# carberry.net
KiCad netlist of a schematic drawn in EAGLE
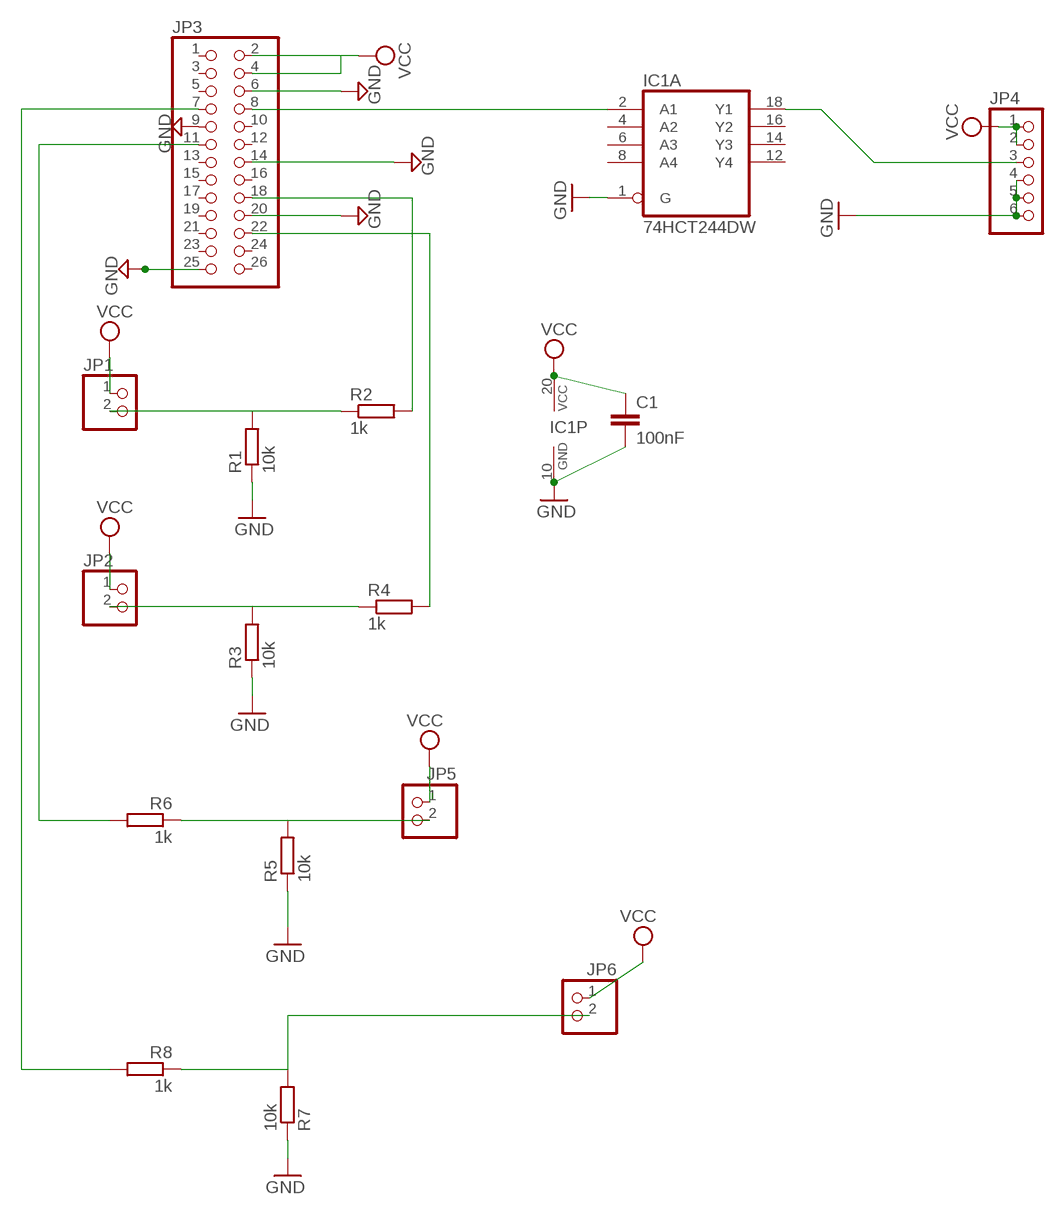
[diagram p0: schematic, sheet 1]

(export (version "E")
  (design (tool "Eeschema 10.0.6"))
  (components
    (comp (ref "C1")
      (value "100nF")
      (footprint "eagle-import:C0603K")
      (libsource (lib "eagle-import") (part "C-EUC0603K"))
    )
    (comp (ref "IC1")
      (value "74HCT244DW")
      (footprint "eagle-import:SO20W")
      (libsource (lib "eagle-import") (part "74244DWHCT"))
    )
    (comp (ref "JP1")
      (value "PINHD-1X2")
      (footprint "eagle-import:1X02")
      (libsource (lib "eagle-import") (part "PINHD-1X2"))
    )
    (comp (ref "JP2")
      (value "PINHD-1X2")
      (footprint "eagle-import:1X02")
      (libsource (lib "eagle-import") (part "PINHD-1X2"))
    )
    (comp (ref "JP3")
      (value "PINHD-2X13")
      (footprint "eagle-import:2X13")
      (libsource (lib "eagle-import") (part "PINHD-2X13"))
    )
    (comp (ref "JP4")
      (value "PINHD-1X6")
      (footprint "eagle-import:1X06")
      (libsource (lib "eagle-import") (part "PINHD-1X6"))
    )
    (comp (ref "JP5")
      (value "PINHD-1X2")
      (footprint "eagle-import:1X02")
      (libsource (lib "eagle-import") (part "PINHD-1X2"))
    )
    (comp (ref "JP6")
      (value "PINHD-1X2")
      (footprint "eagle-import:1X02")
      (libsource (lib "eagle-import") (part "PINHD-1X2"))
    )
    (comp (ref "R1")
      (value "10k")
      (footprint "eagle-import:R0603")
      (libsource (lib "eagle-import") (part "RR0603"))
    )
    (comp (ref "R2")
      (value "1k")
      (footprint "eagle-import:R0603")
      (libsource (lib "eagle-import") (part "RR0603"))
    )
    (comp (ref "R3")
      (value "10k")
      (footprint "eagle-import:R0603")
      (libsource (lib "eagle-import") (part "RR0603"))
    )
    (comp (ref "R4")
      (value "1k")
      (footprint "eagle-import:R0603")
      (libsource (lib "eagle-import") (part "RR0603"))
    )
    (comp (ref "R5")
      (value "10k")
      (footprint "eagle-import:R0603")
      (libsource (lib "eagle-import") (part "RR0603"))
    )
    (comp (ref "R6")
      (value "1k")
      (footprint "eagle-import:R0603")
      (libsource (lib "eagle-import") (part "RR0603"))
    )
    (comp (ref "R7")
      (value "10k")
      (footprint "eagle-import:R0603")
      (libsource (lib "eagle-import") (part "RR0603"))
    )
    (comp (ref "R8")
      (value "1k")
      (footprint "eagle-import:R0603")
      (libsource (lib "eagle-import") (part "RR0603"))
    )
  )
  (nets
    (net (code "1") (name "GND") (class "Default")
      (node (ref "C1") (pin "2") (pinfunction "2_2") (pintype "passive"))
      (node (ref "IC1") (pin "1") (pinfunction "G_1") (pintype "input"))
      (node (ref "IC1") (pin "10") (pinfunction "GND_10") (pintype "power_in"))
      (node (ref "JP3") (pin "14") (pinfunction "14_14") (pintype "passive"))
      (node (ref "JP3") (pin "20") (pinfunction "20_20") (pintype "passive"))
      (node (ref "JP3") (pin "25") (pinfunction "25_25") (pintype "passive"))
      (node (ref "JP3") (pin "6") (pinfunction "6_6") (pintype "passive"))
      (node (ref "JP3") (pin "9") (pinfunction "9_9") (pintype "passive"))
      (node (ref "JP4") (pin "4") (pinfunction "4_4") (pintype "passive"))
      (node (ref "JP4") (pin "5") (pinfunction "5_5") (pintype "passive"))
      (node (ref "JP4") (pin "6") (pinfunction "6_6") (pintype "passive"))
      (node (ref "R1") (pin "1") (pinfunction "1_1") (pintype "passive"))
      (node (ref "R3") (pin "1") (pinfunction "1_1") (pintype "passive"))
      (node (ref "R5") (pin "1") (pinfunction "1_1") (pintype "passive"))
      (node (ref "R7") (pin "1") (pinfunction "1_1") (pintype "passive"))
    )
    (net (code "2") (name "Net-(IC1A-A1)") (class "Default")
      (node (ref "IC1") (pin "2") (pinfunction "A1_2") (pintype "input"))
      (node (ref "JP3") (pin "8") (pinfunction "8_8") (pintype "passive"))
    )
    (net (code "3") (name "Net-(IC1A-Y1)") (class "Default")
      (node (ref "IC1") (pin "18") (pinfunction "Y1_18") (pintype "tri_state"))
      (node (ref "JP4") (pin "3") (pinfunction "3_3") (pintype "passive"))
    )
    (net (code "4") (name "Net-(JP1-Pad2)") (class "Default")
      (node (ref "JP1") (pin "2") (pinfunction "2_2") (pintype "passive"))
      (node (ref "R1") (pin "2") (pinfunction "2_2") (pintype "passive"))
      (node (ref "R2") (pin "1") (pinfunction "1_1") (pintype "passive"))
    )
    (net (code "5") (name "Net-(JP2-Pad2)") (class "Default")
      (node (ref "JP2") (pin "2") (pinfunction "2_2") (pintype "passive"))
      (node (ref "R3") (pin "2") (pinfunction "2_2") (pintype "passive"))
      (node (ref "R4") (pin "1") (pinfunction "1_1") (pintype "passive"))
    )
    (net (code "6") (name "Net-(JP3-Pad7)") (class "Default")
      (node (ref "JP3") (pin "7") (pinfunction "7_7") (pintype "passive"))
      (node (ref "R8") (pin "2") (pinfunction "2_2") (pintype "passive"))
    )
    (net (code "7") (name "Net-(JP3-Pad11)") (class "Default")
      (node (ref "JP3") (pin "11") (pinfunction "11_11") (pintype "passive"))
      (node (ref "R6") (pin "2") (pinfunction "2_2") (pintype "passive"))
    )
    (net (code "8") (name "Net-(JP3-Pad18)") (class "Default")
      (node (ref "JP3") (pin "18") (pinfunction "18_18") (pintype "passive"))
      (node (ref "R2") (pin "2") (pinfunction "2_2") (pintype "passive"))
    )
    (net (code "9") (name "Net-(JP3-Pad22)") (class "Default")
      (node (ref "JP3") (pin "22") (pinfunction "22_22") (pintype "passive"))
      (node (ref "R4") (pin "2") (pinfunction "2_2") (pintype "passive"))
    )
    (net (code "10") (name "Net-(JP5-Pad2)") (class "Default")
      (node (ref "JP5") (pin "2") (pinfunction "2_2") (pintype "passive"))
      (node (ref "R5") (pin "2") (pinfunction "2_2") (pintype "passive"))
      (node (ref "R6") (pin "1") (pinfunction "1_1") (pintype "passive"))
    )
    (net (code "11") (name "Net-(JP6-Pad2)") (class "Default")
      (node (ref "JP6") (pin "2") (pinfunction "2_2") (pintype "passive"))
      (node (ref "R7") (pin "2") (pinfunction "2_2") (pintype "passive"))
      (node (ref "R8") (pin "1") (pinfunction "1_1") (pintype "passive"))
    )
    (net (code "12") (name "VCC") (class "Default")
      (node (ref "C1") (pin "1") (pinfunction "1_1") (pintype "passive"))
      (node (ref "IC1") (pin "20") (pinfunction "VCC_20") (pintype "power_in"))
      (node (ref "JP1") (pin "1") (pinfunction "1_1") (pintype "passive"))
      (node (ref "JP2") (pin "1") (pinfunction "1_1") (pintype "passive"))
      (node (ref "JP3") (pin "2") (pinfunction "2_2") (pintype "passive"))
      (node (ref "JP3") (pin "4") (pinfunction "4_4") (pintype "passive"))
      (node (ref "JP4") (pin "1") (pinfunction "1_1") (pintype "passive"))
      (node (ref "JP4") (pin "2") (pinfunction "2_2") (pintype "passive"))
      (node (ref "JP5") (pin "1") (pinfunction "1_1") (pintype "passive"))
      (node (ref "JP6") (pin "1") (pinfunction "1_1") (pintype "passive"))
    )
    (net (code "13") (name "unconnected-(IC1A-A2-Pad4)") (class "Default")
      (node (ref "IC1") (pin "4") (pinfunction "A2_4") (pintype "input"))
    )
    (net (code "14") (name "unconnected-(IC1A-A3-Pad6)") (class "Default")
      (node (ref "IC1") (pin "6") (pinfunction "A3_6") (pintype "input"))
    )
    (net (code "15") (name "unconnected-(IC1A-A4-Pad8)") (class "Default")
      (node (ref "IC1") (pin "8") (pinfunction "A4_8") (pintype "input"))
    )
    (net (code "16") (name "unconnected-(IC1A-Y2-Pad16)") (class "Default")
      (node (ref "IC1") (pin "16") (pinfunction "Y2_16") (pintype "tri_state"))
    )
    (net (code "17") (name "unconnected-(IC1A-Y3-Pad14)") (class "Default")
      (node (ref "IC1") (pin "14") (pinfunction "Y3_14") (pintype "tri_state"))
    )
    (net (code "18") (name "unconnected-(IC1A-Y4-Pad12)") (class "Default")
      (node (ref "IC1") (pin "12") (pinfunction "Y4_12") (pintype "tri_state"))
    )
    (net (code "19") (name "unconnected-(JP3-Pad1)") (class "Default")
      (node (ref "JP3") (pin "1") (pinfunction "1_1") (pintype "passive"))
    )
    (net (code "20") (name "unconnected-(JP3-Pad3)") (class "Default")
      (node (ref "JP3") (pin "3") (pinfunction "3_3") (pintype "passive"))
    )
    (net (code "21") (name "unconnected-(JP3-Pad5)") (class "Default")
      (node (ref "JP3") (pin "5") (pinfunction "5_5") (pintype "passive"))
    )
    (net (code "22") (name "unconnected-(JP3-Pad10)") (class "Default")
      (node (ref "JP3") (pin "10") (pinfunction "10_10") (pintype "passive"))
    )
    (net (code "23") (name "unconnected-(JP3-Pad12)") (class "Default")
      (node (ref "JP3") (pin "12") (pinfunction "12_12") (pintype "passive"))
    )
    (net (code "24") (name "unconnected-(JP3-Pad13)") (class "Default")
      (node (ref "JP3") (pin "13") (pinfunction "13_13") (pintype "passive"))
    )
    (net (code "25") (name "unconnected-(JP3-Pad15)") (class "Default")
      (node (ref "JP3") (pin "15") (pinfunction "15_15") (pintype "passive"))
    )
    (net (code "26") (name "unconnected-(JP3-Pad16)") (class "Default")
      (node (ref "JP3") (pin "16") (pinfunction "16_16") (pintype "passive"))
    )
    (net (code "27") (name "unconnected-(JP3-Pad17)") (class "Default")
      (node (ref "JP3") (pin "17") (pinfunction "17_17") (pintype "passive"))
    )
    (net (code "28") (name "unconnected-(JP3-Pad19)") (class "Default")
      (node (ref "JP3") (pin "19") (pinfunction "19_19") (pintype "passive"))
    )
    (net (code "29") (name "unconnected-(JP3-Pad21)") (class "Default")
      (node (ref "JP3") (pin "21") (pinfunction "21_21") (pintype "passive"))
    )
    (net (code "30") (name "unconnected-(JP3-Pad23)") (class "Default")
      (node (ref "JP3") (pin "23") (pinfunction "23_23") (pintype "passive"))
    )
    (net (code "31") (name "unconnected-(JP3-Pad24)") (class "Default")
      (node (ref "JP3") (pin "24") (pinfunction "24_24") (pintype "passive"))
    )
    (net (code "32") (name "unconnected-(JP3-Pad26)") (class "Default")
      (node (ref "JP3") (pin "26") (pinfunction "26_26") (pintype "passive"))
    )
  )
)
